# 20240511-sn76489-kempton-ver1.net
KiCad netlist of a schematic drawn in EAGLE
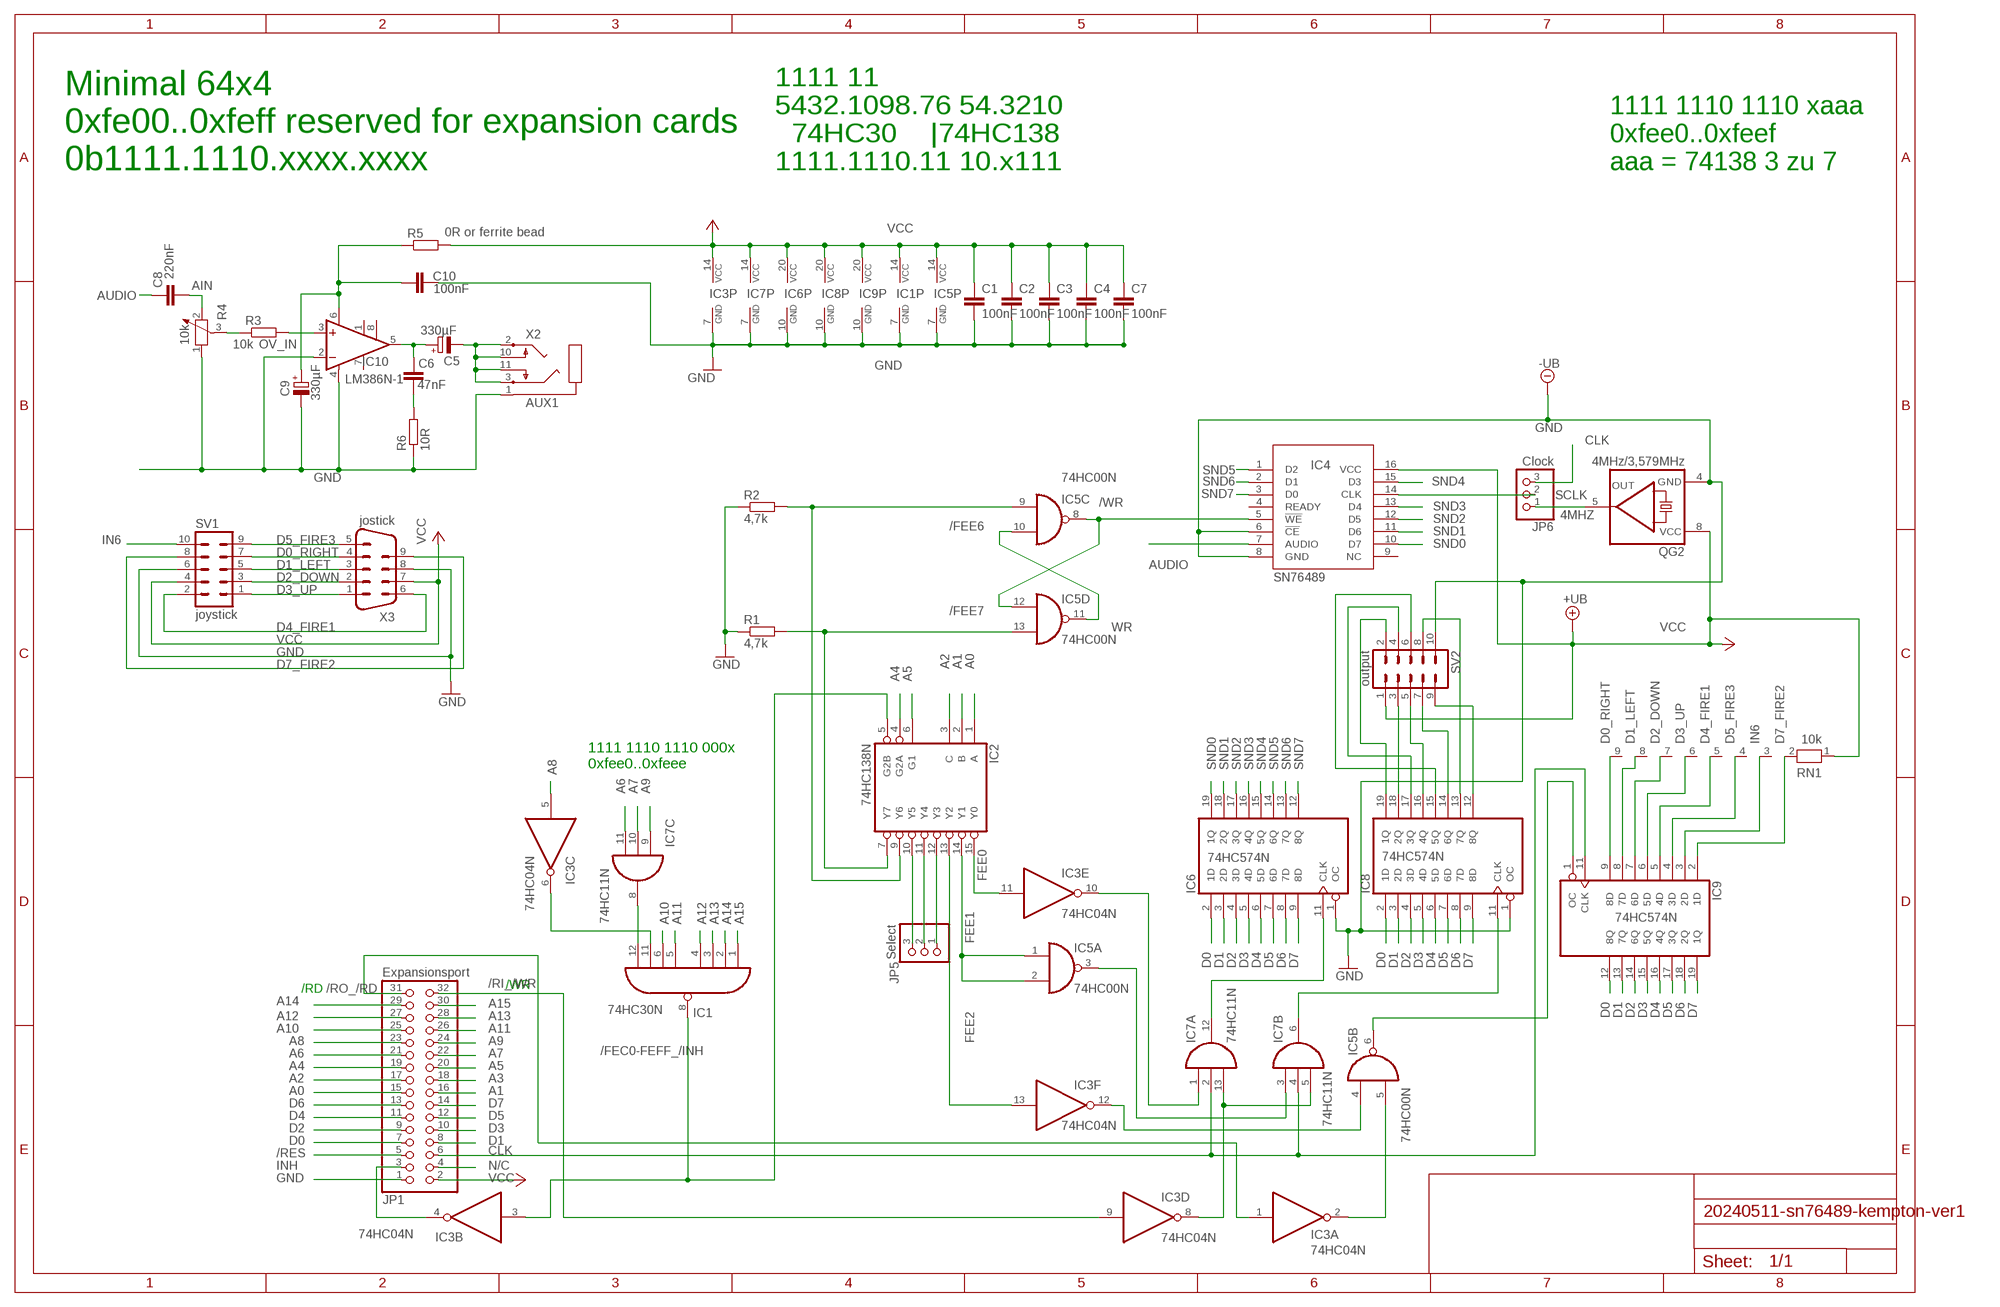
[diagram p0: schematic, sheet 1]

(export (version "E")
  (design (tool "Eeschema 10.0.6"))
  (components
    (comp (ref "C1")
      (value "100nF")
      (footprint "eagle-import:C050-025X075")
      (libsource (lib "eagle-import") (part "C-EU050-025X075"))
    )
    (comp (ref "C2")
      (value "100nF")
      (footprint "eagle-import:C050-025X075")
      (libsource (lib "eagle-import") (part "C-EU050-025X075"))
    )
    (comp (ref "C3")
      (value "100nF")
      (footprint "eagle-import:C050-025X075")
      (libsource (lib "eagle-import") (part "C-EU050-025X075"))
    )
    (comp (ref "C4")
      (value "100nF")
      (footprint "eagle-import:C050-025X075")
      (libsource (lib "eagle-import") (part "C-EU050-025X075"))
    )
    (comp (ref "C5")
      (value "330µF")
      (footprint "eagle-import:E2,5-7")
      (libsource (lib "eagle-import") (part "CPOL-EUE2.5-7"))
    )
    (comp (ref "C6")
      (value "47nF")
      (footprint "eagle-import:C050-025X075")
      (libsource (lib "eagle-import") (part "C-EU050-025X075"))
    )
    (comp (ref "C7")
      (value "100nF")
      (footprint "eagle-import:C050-025X075")
      (libsource (lib "eagle-import") (part "C-EU050-025X075"))
    )
    (comp (ref "C8")
      (value "220nF")
      (footprint "eagle-import:C050-025X075")
      (libsource (lib "eagle-import") (part "C-EU050-025X075"))
    )
    (comp (ref "C9")
      (value "330µF")
      (footprint "eagle-import:E2,5-7")
      (libsource (lib "eagle-import") (part "CPOL-EUE2.5-7"))
    )
    (comp (ref "C10")
      (value "100nF")
      (footprint "eagle-import:C050-025X075")
      (libsource (lib "eagle-import") (part "C-EU050-025X075"))
    )
    (comp (ref "IC1")
      (value "74HC30N")
      (footprint "eagle-import:DIL14")
      (libsource (lib "eagle-import") (part "7430NHC"))
    )
    (comp (ref "IC2")
      (value "74HC138N")
      (footprint "eagle-import:DIL16")
      (libsource (lib "eagle-import") (part "74138NHC"))
    )
    (comp (ref "IC3")
      (value "74HC04N")
      (footprint "eagle-import:DIL14")
      (libsource (lib "eagle-import") (part "7404NHC"))
    )
    (comp (ref "IC4")
      (value "SN76489")
      (footprint "eagle-import:ALEX-PARTS_DIL16")
      (libsource (lib "eagle-import") (part "ALEX-PARTS_SN76489AN"))
    )
    (comp (ref "IC5")
      (value "74HC00N")
      (footprint "eagle-import:DIL14")
      (libsource (lib "eagle-import") (part "7400NHC"))
    )
    (comp (ref "IC6")
      (value "74HC574N")
      (footprint "eagle-import:DIL20")
      (libsource (lib "eagle-import") (part "74574NHC"))
    )
    (comp (ref "IC7")
      (value "74HC11N")
      (footprint "eagle-import:DIL14")
      (libsource (lib "eagle-import") (part "7411NHC"))
    )
    (comp (ref "IC8")
      (value "74HC574N")
      (footprint "eagle-import:DIL20")
      (libsource (lib "eagle-import") (part "74574NHC"))
    )
    (comp (ref "IC9")
      (value "74HC574N")
      (footprint "eagle-import:DIL20")
      (libsource (lib "eagle-import") (part "74574NHC"))
    )
    (comp (ref "IC10")
      (value "LM386N-1")
      (footprint "eagle-import:DIL08")
      (libsource (lib "eagle-import") (part "LM386?-N1"))
    )
    (comp (ref "JP1")
      (value "Expansionsport")
      (footprint "eagle-import:2X16")
      (libsource (lib "eagle-import") (part "PINHD-2X16"))
    )
    (comp (ref "JP5")
      (value "Select")
      (footprint "eagle-import:1X03")
      (libsource (lib "eagle-import") (part "PINHD-1X3"))
    )
    (comp (ref "JP6")
      (value "Clock")
      (footprint "eagle-import:1X03")
      (libsource (lib "eagle-import") (part "PINHD-1X3"))
    )
    (comp (ref "QG2")
      (value "4MHz/3,579MHz")
      (footprint "eagle-import:DIL08S")
      (libsource (lib "eagle-import") (part "QG5460"))
    )
    (comp (ref "R1")
      (value "4,7k")
      (footprint "eagle-import:0207_10")
      (libsource (lib "eagle-import") (part "R-EU_0207/10"))
    )
    (comp (ref "R2")
      (value "4,7k")
      (footprint "eagle-import:0207_10")
      (libsource (lib "eagle-import") (part "R-EU_0207/10"))
    )
    (comp (ref "R3")
      (value "10k")
      (footprint "eagle-import:0207_10")
      (libsource (lib "eagle-import") (part "R-EU_0207/10"))
    )
    (comp (ref "R4")
      (value "10k")
      (footprint "eagle-import:PT-10S")
      (libsource (lib "eagle-import") (part "POTENTIOMETER_PT-10S"))
    )
    (comp (ref "R5")
      (value "0R or ferrite bead")
      (footprint "eagle-import:0207_10")
      (libsource (lib "eagle-import") (part "R-EU_0207/10"))
    )
    (comp (ref "R6")
      (value "10R")
      (footprint "eagle-import:0207_10")
      (libsource (lib "eagle-import") (part "R-EU_0207/10"))
    )
    (comp (ref "RN1")
      (value "10k")
      (footprint "eagle-import:RN-9")
      (libsource (lib "eagle-import") (part "RN08"))
    )
    (comp (ref "SV1")
      (value "joystick")
      (footprint "eagle-import:ML10")
      (libsource (lib "eagle-import") (part "ML10"))
    )
    (comp (ref "SV2")
      (value "output")
      (footprint "eagle-import:ML10")
      (libsource (lib "eagle-import") (part "ML10"))
    )
    (comp (ref "X2")
      (value "AUX1")
      (footprint "eagle-import:SJ1-352XN")
      (libsource (lib "eagle-import") (part "CON-SJ1-352XNSJ1-352XN"))
    )
    (comp (ref "X3")
      (value "jostick")
      (footprint "eagle-import:182-009-MALE")
      (libsource (lib "eagle-import") (part "M09-182"))
    )
  )
  (nets
    (net (code "1") (name "+UB") (class "Default")
      (node (ref "C1") (pin "1") (pinfunction "1_1") (pintype "passive"))
      (node (ref "C2") (pin "1") (pinfunction "1_1") (pintype "passive"))
      (node (ref "C3") (pin "1") (pinfunction "1_1") (pintype "passive"))
      (node (ref "C4") (pin "1") (pinfunction "1_1") (pintype "passive"))
      (node (ref "C7") (pin "1") (pinfunction "1_1") (pintype "passive"))
      (node (ref "IC1") (pin "14") (pinfunction "VCC_14") (pintype "power_in"))
      (node (ref "IC3") (pin "14") (pinfunction "VCC_14") (pintype "power_in"))
      (node (ref "IC4") (pin "16") (pinfunction "VCC_16") (pintype "input"))
      (node (ref "IC5") (pin "14") (pinfunction "VCC_14") (pintype "power_in"))
      (node (ref "IC6") (pin "20") (pinfunction "VCC_20") (pintype "power_in"))
      (node (ref "IC7") (pin "14") (pinfunction "VCC_14") (pintype "power_in"))
      (node (ref "IC8") (pin "20") (pinfunction "VCC_20") (pintype "power_in"))
      (node (ref "IC9") (pin "20") (pinfunction "VCC_20") (pintype "power_in"))
      (node (ref "JP1") (pin "2") (pinfunction "2_2") (pintype "passive"))
      (node (ref "QG2") (pin "8") (pinfunction "VCC_8") (pintype "power_in"))
      (node (ref "R5") (pin "2") (pinfunction "2_2") (pintype "passive"))
      (node (ref "RN1") (pin "1") (pinfunction "1_1") (pintype "passive"))
      (node (ref "SV1") (pin "4") (pinfunction "4_4") (pintype "passive"))
      (node (ref "SV2") (pin "1") (pinfunction "1_1") (pintype "passive"))
      (node (ref "X3") (pin "7") (pinfunction "7_7") (pintype "passive"))
    )
    (net (code "2") (name "-UB") (class "Default")
      (node (ref "C1") (pin "2") (pinfunction "2_2") (pintype "passive"))
      (node (ref "C10") (pin "2") (pinfunction "2_2") (pintype "passive"))
      (node (ref "C2") (pin "2") (pinfunction "2_2") (pintype "passive"))
      (node (ref "C3") (pin "2") (pinfunction "2_2") (pintype "passive"))
      (node (ref "C4") (pin "2") (pinfunction "2_2") (pintype "passive"))
      (node (ref "C7") (pin "2") (pinfunction "2_2") (pintype "passive"))
      (node (ref "C9") (pin "-") (pinfunction "-_-") (pintype "passive"))
      (node (ref "IC1") (pin "7") (pinfunction "GND_7") (pintype "power_in"))
      (node (ref "IC10") (pin "2") (pinfunction "-IN_2") (pintype "input"))
      (node (ref "IC10") (pin "4") (pinfunction "GND_4") (pintype "power_in"))
      (node (ref "IC3") (pin "7") (pinfunction "GND_7") (pintype "power_in"))
      (node (ref "IC4") (pin "6") (pinfunction "~{CE}_6") (pintype "input"))
      (node (ref "IC4") (pin "8") (pinfunction "GND_8") (pintype "power_in"))
      (node (ref "IC5") (pin "7") (pinfunction "GND_7") (pintype "power_in"))
      (node (ref "IC6") (pin "1") (pinfunction "OC_1") (pintype "input"))
      (node (ref "IC6") (pin "10") (pinfunction "GND_10") (pintype "power_in"))
      (node (ref "IC7") (pin "7") (pinfunction "GND_7") (pintype "power_in"))
      (node (ref "IC8") (pin "1") (pinfunction "OC_1") (pintype "input"))
      (node (ref "IC8") (pin "10") (pinfunction "GND_10") (pintype "power_in"))
      (node (ref "IC9") (pin "10") (pinfunction "GND_10") (pintype "power_in"))
      (node (ref "JP1") (pin "1") (pinfunction "1_1") (pintype "passive"))
      (node (ref "QG2") (pin "4") (pinfunction "GND_4") (pintype "power_in"))
      (node (ref "R1") (pin "1") (pinfunction "1_1") (pintype "passive"))
      (node (ref "R2") (pin "1") (pinfunction "1_1") (pintype "passive"))
      (node (ref "R4") (pin "1") (pinfunction "1_1") (pintype "passive"))
      (node (ref "R6") (pin "1") (pinfunction "1_1") (pintype "passive"))
      (node (ref "SV1") (pin "6") (pinfunction "6_6") (pintype "passive"))
      (node (ref "SV2") (pin "10") (pinfunction "10_10") (pintype "passive"))
      (node (ref "X2") (pin "1") (pinfunction "1_1") (pintype "passive"))
      (node (ref "X3") (pin "8") (pinfunction "8_8") (pintype "passive"))
    )
    (net (code "3") (name "/4MHZ") (class "Default")
      (node (ref "JP6") (pin "1") (pinfunction "1_1") (pintype "passive"))
      (node (ref "QG2") (pin "5") (pinfunction "OUT_5") (pintype "output"))
    )
    (net (code "4") (name "/A0") (class "Default")
      (node (ref "IC2") (pin "1") (pinfunction "A_1") (pintype "input"))
      (node (ref "JP1") (pin "15") (pinfunction "15_15") (pintype "passive"))
    )
    (net (code "5") (name "/A1") (class "Default")
      (node (ref "IC2") (pin "2") (pinfunction "B_2") (pintype "input"))
      (node (ref "JP1") (pin "16") (pinfunction "16_16") (pintype "passive"))
    )
    (net (code "6") (name "/A2") (class "Default")
      (node (ref "IC2") (pin "3") (pinfunction "C_3") (pintype "input"))
      (node (ref "JP1") (pin "17") (pinfunction "17_17") (pintype "passive"))
    )
    (net (code "7") (name "/A3") (class "Default")
      (node (ref "JP1") (pin "18") (pinfunction "18_18") (pintype "passive"))
    )
    (net (code "8") (name "/A4") (class "Default")
      (node (ref "IC2") (pin "4") (pinfunction "G2A_4") (pintype "input"))
      (node (ref "JP1") (pin "19") (pinfunction "19_19") (pintype "passive"))
    )
    (net (code "9") (name "/A5") (class "Default")
      (node (ref "IC2") (pin "6") (pinfunction "G1_6") (pintype "input"))
      (node (ref "JP1") (pin "20") (pinfunction "20_20") (pintype "passive"))
    )
    (net (code "10") (name "/A6") (class "Default")
      (node (ref "IC7") (pin "11") (pinfunction "I2_11") (pintype "input"))
      (node (ref "JP1") (pin "21") (pinfunction "21_21") (pintype "passive"))
    )
    (net (code "11") (name "/A7") (class "Default")
      (node (ref "IC7") (pin "10") (pinfunction "I1_10") (pintype "input"))
      (node (ref "JP1") (pin "22") (pinfunction "22_22") (pintype "passive"))
    )
    (net (code "12") (name "/A8") (class "Default")
      (node (ref "IC3") (pin "5") (pinfunction "I_5") (pintype "input"))
      (node (ref "JP1") (pin "23") (pinfunction "23_23") (pintype "passive"))
    )
    (net (code "13") (name "/A9") (class "Default")
      (node (ref "IC7") (pin "9") (pinfunction "I0_9") (pintype "input"))
      (node (ref "JP1") (pin "24") (pinfunction "24_24") (pintype "passive"))
    )
    (net (code "14") (name "/A10") (class "Default")
      (node (ref "IC1") (pin "6") (pinfunction "I5_6") (pintype "input"))
      (node (ref "JP1") (pin "25") (pinfunction "25_25") (pintype "passive"))
    )
    (net (code "15") (name "/A11") (class "Default")
      (node (ref "IC1") (pin "5") (pinfunction "I4_5") (pintype "input"))
      (node (ref "JP1") (pin "26") (pinfunction "26_26") (pintype "passive"))
    )
    (net (code "16") (name "/A12") (class "Default")
      (node (ref "IC1") (pin "4") (pinfunction "I3_4") (pintype "input"))
      (node (ref "JP1") (pin "27") (pinfunction "27_27") (pintype "passive"))
    )
    (net (code "17") (name "/A13") (class "Default")
      (node (ref "IC1") (pin "3") (pinfunction "I2_3") (pintype "input"))
      (node (ref "JP1") (pin "28") (pinfunction "28_28") (pintype "passive"))
    )
    (net (code "18") (name "/A14") (class "Default")
      (node (ref "IC1") (pin "2") (pinfunction "I1_2") (pintype "input"))
      (node (ref "JP1") (pin "29") (pinfunction "29_29") (pintype "passive"))
    )
    (net (code "19") (name "/A15") (class "Default")
      (node (ref "IC1") (pin "1") (pinfunction "I0_1") (pintype "input"))
      (node (ref "JP1") (pin "30") (pinfunction "30_30") (pintype "passive"))
    )
    (net (code "20") (name "/AIN") (class "Default")
      (node (ref "C8") (pin "2") (pinfunction "2_2") (pintype "passive"))
      (node (ref "R4") (pin "2") (pinfunction "2_2") (pintype "passive"))
    )
    (net (code "21") (name "/AUDIO") (class "Default")
      (node (ref "C8") (pin "1") (pinfunction "1_1") (pintype "passive"))
      (node (ref "IC4") (pin "7") (pinfunction "AUDIO_7") (pintype "output"))
    )
    (net (code "22") (name "/CLK") (class "Default")
      (node (ref "IC7") (pin "2") (pinfunction "I1_2") (pintype "input"))
      (node (ref "IC7") (pin "4") (pinfunction "I1_4") (pintype "input"))
      (node (ref "IC9") (pin "11") (pinfunction "CLK_11") (pintype "input"))
      (node (ref "JP1") (pin "6") (pinfunction "6_6") (pintype "passive"))
      (node (ref "JP6") (pin "3") (pinfunction "3_3") (pintype "passive"))
    )
    (net (code "23") (name "/D0") (class "Default")
      (node (ref "IC6") (pin "2") (pinfunction "1D_2") (pintype "input"))
      (node (ref "IC8") (pin "2") (pinfunction "1D_2") (pintype "input"))
      (node (ref "IC9") (pin "12") (pinfunction "8Q_12") (pintype "tri_state"))
      (node (ref "JP1") (pin "7") (pinfunction "7_7") (pintype "passive"))
    )
    (net (code "24") (name "/D0_RIGHT") (class "Default")
      (node (ref "IC9") (pin "9") (pinfunction "8D_9") (pintype "input"))
      (node (ref "RN1") (pin "9") (pinfunction "9_9") (pintype "passive"))
      (node (ref "SV1") (pin "7") (pinfunction "7_7") (pintype "passive"))
      (node (ref "X3") (pin "4") (pinfunction "4_4") (pintype "passive"))
    )
    (net (code "25") (name "/D1") (class "Default")
      (node (ref "IC6") (pin "3") (pinfunction "2D_3") (pintype "input"))
      (node (ref "IC8") (pin "3") (pinfunction "2D_3") (pintype "input"))
      (node (ref "IC9") (pin "13") (pinfunction "7Q_13") (pintype "tri_state"))
      (node (ref "JP1") (pin "8") (pinfunction "8_8") (pintype "passive"))
    )
    (net (code "26") (name "/D1_LEFT") (class "Default")
      (node (ref "IC9") (pin "8") (pinfunction "7D_8") (pintype "input"))
      (node (ref "RN1") (pin "8") (pinfunction "8_8") (pintype "passive"))
      (node (ref "SV1") (pin "5") (pinfunction "5_5") (pintype "passive"))
      (node (ref "X3") (pin "3") (pinfunction "3_3") (pintype "passive"))
    )
    (net (code "27") (name "/D2") (class "Default")
      (node (ref "IC6") (pin "4") (pinfunction "3D_4") (pintype "input"))
      (node (ref "IC8") (pin "4") (pinfunction "3D_4") (pintype "input"))
      (node (ref "IC9") (pin "14") (pinfunction "6Q_14") (pintype "tri_state"))
      (node (ref "JP1") (pin "9") (pinfunction "9_9") (pintype "passive"))
    )
    (net (code "28") (name "/D2_DOWN") (class "Default")
      (node (ref "IC9") (pin "7") (pinfunction "6D_7") (pintype "input"))
      (node (ref "RN1") (pin "7") (pinfunction "7_7") (pintype "passive"))
      (node (ref "SV1") (pin "3") (pinfunction "3_3") (pintype "passive"))
      (node (ref "X3") (pin "2") (pinfunction "2_2") (pintype "passive"))
    )
    (net (code "29") (name "/D3") (class "Default")
      (node (ref "IC6") (pin "5") (pinfunction "4D_5") (pintype "input"))
      (node (ref "IC8") (pin "5") (pinfunction "4D_5") (pintype "input"))
      (node (ref "IC9") (pin "15") (pinfunction "5Q_15") (pintype "tri_state"))
      (node (ref "JP1") (pin "10") (pinfunction "10_10") (pintype "passive"))
    )
    (net (code "30") (name "/D3_UP") (class "Default")
      (node (ref "IC9") (pin "6") (pinfunction "5D_6") (pintype "input"))
      (node (ref "RN1") (pin "6") (pinfunction "6_6") (pintype "passive"))
      (node (ref "SV1") (pin "1") (pinfunction "1_1") (pintype "passive"))
      (node (ref "X3") (pin "1") (pinfunction "1_1") (pintype "passive"))
    )
    (net (code "31") (name "/D4") (class "Default")
      (node (ref "IC6") (pin "6") (pinfunction "5D_6") (pintype "input"))
      (node (ref "IC8") (pin "6") (pinfunction "5D_6") (pintype "input"))
      (node (ref "IC9") (pin "16") (pinfunction "4Q_16") (pintype "tri_state"))
      (node (ref "JP1") (pin "11") (pinfunction "11_11") (pintype "passive"))
    )
    (net (code "32") (name "/D4_FIRE1") (class "Default")
      (node (ref "IC9") (pin "5") (pinfunction "4D_5") (pintype "input"))
      (node (ref "RN1") (pin "5") (pinfunction "5_5") (pintype "passive"))
      (node (ref "SV1") (pin "2") (pinfunction "2_2") (pintype "passive"))
      (node (ref "X3") (pin "6") (pinfunction "6_6") (pintype "passive"))
    )
    (net (code "33") (name "/D5") (class "Default")
      (node (ref "IC6") (pin "7") (pinfunction "6D_7") (pintype "input"))
      (node (ref "IC8") (pin "7") (pinfunction "6D_7") (pintype "input"))
      (node (ref "IC9") (pin "17") (pinfunction "3Q_17") (pintype "tri_state"))
      (node (ref "JP1") (pin "12") (pinfunction "12_12") (pintype "passive"))
    )
    (net (code "34") (name "/D5_FIRE3") (class "Default")
      (node (ref "IC9") (pin "4") (pinfunction "3D_4") (pintype "input"))
      (node (ref "RN1") (pin "4") (pinfunction "4_4") (pintype "passive"))
      (node (ref "SV1") (pin "9") (pinfunction "9_9") (pintype "passive"))
      (node (ref "X3") (pin "5") (pinfunction "5_5") (pintype "passive"))
    )
    (net (code "35") (name "/D6") (class "Default")
      (node (ref "IC6") (pin "8") (pinfunction "7D_8") (pintype "input"))
      (node (ref "IC8") (pin "8") (pinfunction "7D_8") (pintype "input"))
      (node (ref "IC9") (pin "18") (pinfunction "2Q_18") (pintype "tri_state"))
      (node (ref "JP1") (pin "13") (pinfunction "13_13") (pintype "passive"))
    )
    (net (code "36") (name "/D7") (class "Default")
      (node (ref "IC6") (pin "9") (pinfunction "8D_9") (pintype "input"))
      (node (ref "IC8") (pin "9") (pinfunction "8D_9") (pintype "input"))
      (node (ref "IC9") (pin "19") (pinfunction "1Q_19") (pintype "tri_state"))
      (node (ref "JP1") (pin "14") (pinfunction "14_14") (pintype "passive"))
    )
    (net (code "37") (name "/D7_FIRE2") (class "Default")
      (node (ref "IC9") (pin "2") (pinfunction "1D_2") (pintype "input"))
      (node (ref "RN1") (pin "2") (pinfunction "2_2") (pintype "passive"))
      (node (ref "SV1") (pin "8") (pinfunction "8_8") (pintype "passive"))
      (node (ref "X3") (pin "9") (pinfunction "9_9") (pintype "passive"))
    )
    (net (code "38") (name "/FEE0") (class "Default")
      (node (ref "IC2") (pin "15") (pinfunction "Y0_15") (pintype "output"))
      (node (ref "IC3") (pin "11") (pinfunction "I_11") (pintype "input"))
    )
    (net (code "39") (name "/FEE1") (class "Default")
      (node (ref "IC2") (pin "14") (pinfunction "Y1_14") (pintype "output"))
      (node (ref "IC5") (pin "1") (pinfunction "I0_1") (pintype "input"))
      (node (ref "IC5") (pin "2") (pinfunction "I1_2") (pintype "input"))
    )
    (net (code "40") (name "/FEE2") (class "Default")
      (node (ref "IC3") (pin "12") (pinfunction "O_12") (pintype "output"))
      (node (ref "IC5") (pin "4") (pinfunction "I0_4") (pintype "input"))
    )
    (net (code "41") (name "/IN6") (class "Default")
      (node (ref "IC9") (pin "3") (pinfunction "2D_3") (pintype "input"))
      (node (ref "RN1") (pin "3") (pinfunction "3_3") (pintype "passive"))
      (node (ref "SV1") (pin "10") (pinfunction "10_10") (pintype "passive"))
    )
    (net (code "42") (name "/INH") (class "Default")
      (node (ref "IC3") (pin "4") (pinfunction "O_4") (pintype "output"))
      (node (ref "JP1") (pin "3") (pinfunction "3_3") (pintype "passive"))
    )
    (net (code "43") (name "/N{slash}C") (class "Default")
      (node (ref "JP1") (pin "4") (pinfunction "4_4") (pintype "passive"))
    )
    (net (code "44") (name "/OV_IN") (class "Default")
      (node (ref "IC10") (pin "3") (pinfunction "+IN_3") (pintype "input"))
      (node (ref "R3") (pin "2") (pinfunction "2_2") (pintype "passive"))
    )
    (net (code "45") (name "/SCLK") (class "Default")
      (node (ref "IC4") (pin "14") (pinfunction "CLK_14") (pintype "input"))
      (node (ref "JP6") (pin "2") (pinfunction "2_2") (pintype "passive"))
    )
    (net (code "46") (name "/SND0") (class "Default")
      (node (ref "IC4") (pin "10") (pinfunction "D7_10") (pintype "input"))
      (node (ref "IC6") (pin "19") (pinfunction "1Q_19") (pintype "tri_state"))
    )
    (net (code "47") (name "/SND1") (class "Default")
      (node (ref "IC4") (pin "11") (pinfunction "D6_11") (pintype "input"))
      (node (ref "IC6") (pin "18") (pinfunction "2Q_18") (pintype "tri_state"))
    )
    (net (code "48") (name "/SND2") (class "Default")
      (node (ref "IC4") (pin "12") (pinfunction "D5_12") (pintype "input"))
      (node (ref "IC6") (pin "17") (pinfunction "3Q_17") (pintype "tri_state"))
    )
    (net (code "49") (name "/SND3") (class "Default")
      (node (ref "IC4") (pin "13") (pinfunction "D4_13") (pintype "input"))
      (node (ref "IC6") (pin "16") (pinfunction "4Q_16") (pintype "tri_state"))
    )
    (net (code "50") (name "/SND4") (class "Default")
      (node (ref "IC4") (pin "15") (pinfunction "D3_15") (pintype "input"))
      (node (ref "IC6") (pin "15") (pinfunction "5Q_15") (pintype "tri_state"))
    )
    (net (code "51") (name "/SND5") (class "Default")
      (node (ref "IC4") (pin "1") (pinfunction "D2_1") (pintype "input"))
      (node (ref "IC6") (pin "14") (pinfunction "6Q_14") (pintype "tri_state"))
    )
    (net (code "52") (name "/SND6") (class "Default")
      (node (ref "IC4") (pin "2") (pinfunction "D1_2") (pintype "input"))
      (node (ref "IC6") (pin "13") (pinfunction "7Q_13") (pintype "tri_state"))
    )
    (net (code "53") (name "/SND7") (class "Default")
      (node (ref "IC4") (pin "3") (pinfunction "D0_3") (pintype "input"))
      (node (ref "IC6") (pin "12") (pinfunction "8Q_12") (pintype "tri_state"))
    )
    (net (code "54") (name "/WR") (class "Default")
      (node (ref "IC5") (pin "10") (pinfunction "I1_10") (pintype "input"))
      (node (ref "IC5") (pin "11") (pinfunction "O_11") (pintype "output"))
    )
    (net (code "55") (name "/{slash}FEC0-FEFF_{slash}INH") (class "Default")
      (node (ref "IC1") (pin "8") (pinfunction "O_8") (pintype "output"))
      (node (ref "IC2") (pin "5") (pinfunction "G2B_5") (pintype "input"))
      (node (ref "IC3") (pin "3") (pinfunction "I_3") (pintype "input"))
    )
    (net (code "56") (name "/{slash}FEE6") (class "Default")
      (node (ref "IC2") (pin "9") (pinfunction "Y6_9") (pintype "output"))
      (node (ref "IC5") (pin "9") (pinfunction "I0_9") (pintype "input"))
      (node (ref "R2") (pin "2") (pinfunction "2_2") (pintype "passive"))
    )
    (net (code "57") (name "/{slash}FEE7") (class "Default")
      (node (ref "IC2") (pin "7") (pinfunction "Y7_7") (pintype "output"))
      (node (ref "IC5") (pin "13") (pinfunction "I1_13") (pintype "input"))
      (node (ref "R1") (pin "2") (pinfunction "2_2") (pintype "passive"))
    )
    (net (code "58") (name "/{slash}RES") (class "Default")
      (node (ref "JP1") (pin "5") (pinfunction "5_5") (pintype "passive"))
    )
    (net (code "59") (name "/{slash}RI_{slash}WR") (class "Default")
      (node (ref "IC3") (pin "9") (pinfunction "I_9") (pintype "input"))
      (node (ref "JP1") (pin "32") (pinfunction "32_32") (pintype "passive"))
    )
    (net (code "60") (name "/{slash}RO_{slash}RD") (class "Default")
      (node (ref "IC3") (pin "1") (pinfunction "I_1") (pintype "input"))
      (node (ref "JP1") (pin "31") (pinfunction "31_31") (pintype "passive"))
    )
    (net (code "61") (name "/{slash}WR") (class "Default")
      (node (ref "IC4") (pin "5") (pinfunction "~{WE}_5") (pintype "input"))
      (node (ref "IC5") (pin "12") (pinfunction "I0_12") (pintype "input"))
      (node (ref "IC5") (pin "8") (pinfunction "O_8") (pintype "output"))
    )
    (net (code "62") (name "Net-(C5-Pad-)") (class "Default")
      (node (ref "C5") (pin "-") (pinfunction "-_-") (pintype "passive"))
      (node (ref "X2") (pin "10") (pinfunction "10_10") (pintype "passive"))
      (node (ref "X2") (pin "11") (pinfunction "11_11") (pintype "passive"))
      (node (ref "X2") (pin "2") (pinfunction "2_2") (pintype "passive"))
      (node (ref "X2") (pin "3") (pinfunction "3_3") (pintype "passive"))
    )
    (net (code "63") (name "Net-(C6-Pad2)") (class "Default")
      (node (ref "C6") (pin "2") (pinfunction "2_2") (pintype "passive"))
      (node (ref "R6") (pin "2") (pinfunction "2_2") (pintype "passive"))
    )
    (net (code "64") (name "Net-(IC1A-I6)") (class "Default")
      (node (ref "IC1") (pin "11") (pinfunction "I6_11") (pintype "input"))
      (node (ref "IC3") (pin "6") (pinfunction "O_6") (pintype "output"))
    )
    (net (code "65") (name "Net-(IC1A-I7)") (class "Default")
      (node (ref "IC1") (pin "12") (pinfunction "I7_12") (pintype "input"))
      (node (ref "IC7") (pin "8") (pinfunction "O_8") (pintype "output"))
    )
    (net (code "66") (name "Net-(IC2A-Y2)") (class "Default")
      (node (ref "IC2") (pin "13") (pinfunction "Y2_13") (pintype "output"))
      (node (ref "IC3") (pin "13") (pinfunction "I_13") (pintype "input"))
    )
    (net (code "67") (name "Net-(IC2A-Y3)") (class "Default")
      (node (ref "IC2") (pin "12") (pinfunction "Y3_12") (pintype "output"))
      (node (ref "JP5") (pin "1") (pinfunction "1_1") (pintype "passive"))
    )
    (net (code "68") (name "Net-(IC2A-Y4)") (class "Default")
      (node (ref "IC2") (pin "11") (pinfunction "Y4_11") (pintype "output"))
      (node (ref "JP5") (pin "2") (pinfunction "2_2") (pintype "passive"))
    )
    (net (code "69") (name "Net-(IC2A-Y5)") (class "Default")
      (node (ref "IC2") (pin "10") (pinfunction "Y5_10") (pintype "output"))
      (node (ref "JP5") (pin "3") (pinfunction "3_3") (pintype "passive"))
    )
    (net (code "70") (name "Net-(IC3A-O)") (class "Default")
      (node (ref "IC3") (pin "2") (pinfunction "O_2") (pintype "output"))
      (node (ref "IC5") (pin "5") (pinfunction "I1_5") (pintype "input"))
    )
    (net (code "71") (name "Net-(IC3D-O)") (class "Default")
      (node (ref "IC3") (pin "8") (pinfunction "O_8") (pintype "output"))
      (node (ref "IC7") (pin "13") (pinfunction "I2_13") (pintype "input"))
      (node (ref "IC7") (pin "5") (pinfunction "I2_5") (pintype "input"))
    )
    (net (code "72") (name "Net-(IC3E-O)") (class "Default")
      (node (ref "IC3") (pin "10") (pinfunction "O_10") (pintype "output"))
      (node (ref "IC7") (pin "1") (pinfunction "I0_1") (pintype "input"))
    )
    (net (code "73") (name "Net-(IC5A-O)") (class "Default")
      (node (ref "IC5") (pin "3") (pinfunction "O_3") (pintype "output"))
      (node (ref "IC7") (pin "3") (pinfunction "I0_3") (pintype "input"))
    )
    (net (code "74") (name "Net-(IC5B-O)") (class "Default")
      (node (ref "IC5") (pin "6") (pinfunction "O_6") (pintype "output"))
      (node (ref "IC9") (pin "1") (pinfunction "OC_1") (pintype "input"))
    )
    (net (code "75") (name "Net-(IC6A-CLK)") (class "Default")
      (node (ref "IC6") (pin "11") (pinfunction "CLK_11") (pintype "input"))
      (node (ref "IC7") (pin "12") (pinfunction "O_12") (pintype "output"))
    )
    (net (code "76") (name "Net-(IC7B-O)") (class "Default")
      (node (ref "IC7") (pin "6") (pinfunction "O_6") (pintype "output"))
      (node (ref "IC8") (pin "11") (pinfunction "CLK_11") (pintype "input"))
    )
    (net (code "77") (name "Net-(IC8A-1Q)") (class "Default")
      (node (ref "IC8") (pin "19") (pinfunction "1Q_19") (pintype "tri_state"))
      (node (ref "SV2") (pin "2") (pinfunction "2_2") (pintype "passive"))
    )
    (net (code "78") (name "Net-(IC8A-2Q)") (class "Default")
      (node (ref "IC8") (pin "18") (pinfunction "2Q_18") (pintype "tri_state"))
      (node (ref "SV2") (pin "3") (pinfunction "3_3") (pintype "passive"))
    )
    (net (code "79") (name "Net-(IC8A-3Q)") (class "Default")
      (node (ref "IC8") (pin "17") (pinfunction "3Q_17") (pintype "tri_state"))
      (node (ref "SV2") (pin "4") (pinfunction "4_4") (pintype "passive"))
    )
    (net (code "80") (name "Net-(IC8A-4Q)") (class "Default")
      (node (ref "IC8") (pin "16") (pinfunction "4Q_16") (pintype "tri_state"))
      (node (ref "SV2") (pin "5") (pinfunction "5_5") (pintype "passive"))
    )
    (net (code "81") (name "Net-(IC8A-5Q)") (class "Default")
      (node (ref "IC8") (pin "15") (pinfunction "5Q_15") (pintype "tri_state"))
      (node (ref "SV2") (pin "6") (pinfunction "6_6") (pintype "passive"))
    )
    (net (code "82") (name "Net-(IC8A-6Q)") (class "Default")
      (node (ref "IC8") (pin "14") (pinfunction "6Q_14") (pintype "tri_state"))
      (node (ref "SV2") (pin "7") (pinfunction "7_7") (pintype "passive"))
    )
    (net (code "83") (name "Net-(IC8A-7Q)") (class "Default")
      (node (ref "IC8") (pin "13") (pinfunction "7Q_13") (pintype "tri_state"))
      (node (ref "SV2") (pin "8") (pinfunction "8_8") (pintype "passive"))
    )
    (net (code "84") (name "Net-(IC8A-8Q)") (class "Default")
      (node (ref "IC8") (pin "12") (pinfunction "8Q_12") (pintype "tri_state"))
      (node (ref "SV2") (pin "9") (pinfunction "9_9") (pintype "passive"))
    )
    (net (code "85") (name "Net-(IC10-OUT)") (class "Default")
      (node (ref "C5") (pin "+") (pinfunction "+_+") (pintype "passive"))
      (node (ref "C6") (pin "1") (pinfunction "1_1") (pintype "passive"))
      (node (ref "IC10") (pin "5") (pinfunction "OUT_5") (pintype "output"))
    )
    (net (code "86") (name "Net-(IC10-VS)") (class "Default")
      (node (ref "C10") (pin "1") (pinfunction "1_1") (pintype "passive"))
      (node (ref "C9") (pin "+") (pinfunction "+_+") (pintype "passive"))
      (node (ref "IC10") (pin "6") (pinfunction "VS_6") (pintype "power_in"))
      (node (ref "R5") (pin "1") (pinfunction "1_1") (pintype "passive"))
    )
    (net (code "87") (name "Net-(R3-Pad1)") (class "Default")
      (node (ref "R3") (pin "1") (pinfunction "1_1") (pintype "passive"))
      (node (ref "R4") (pin "3") (pinfunction "3_3") (pintype "passive"))
    )
    (net (code "88") (name "unconnected-(IC4-NC-Pad9)") (class "Default")
      (node (ref "IC4") (pin "9") (pinfunction "NC_9") (pintype "no_connect"))
    )
    (net (code "89") (name "unconnected-(IC4-READY-Pad4)") (class "Default")
      (node (ref "IC4") (pin "4") (pinfunction "READY_4") (pintype "output"))
    )
    (net (code "90") (name "unconnected-(IC10-BYPASS-Pad7)") (class "Default")
      (node (ref "IC10") (pin "7") (pinfunction "BYPASS_7") (pintype "passive"))
    )
    (net (code "91") (name "unconnected-(IC10-GAIN-Pad1)") (class "Default")
      (node (ref "IC10") (pin "1") (pinfunction "GAIN_1") (pintype "passive"))
    )
    (net (code "92") (name "unconnected-(IC10-GAIN-Pad8)") (class "Default")
      (node (ref "IC10") (pin "8") (pinfunction "GAIN_8") (pintype "passive"))
    )
  )
)
